# Top.net
KiCad netlist of a schematic drawn in Altium Designer
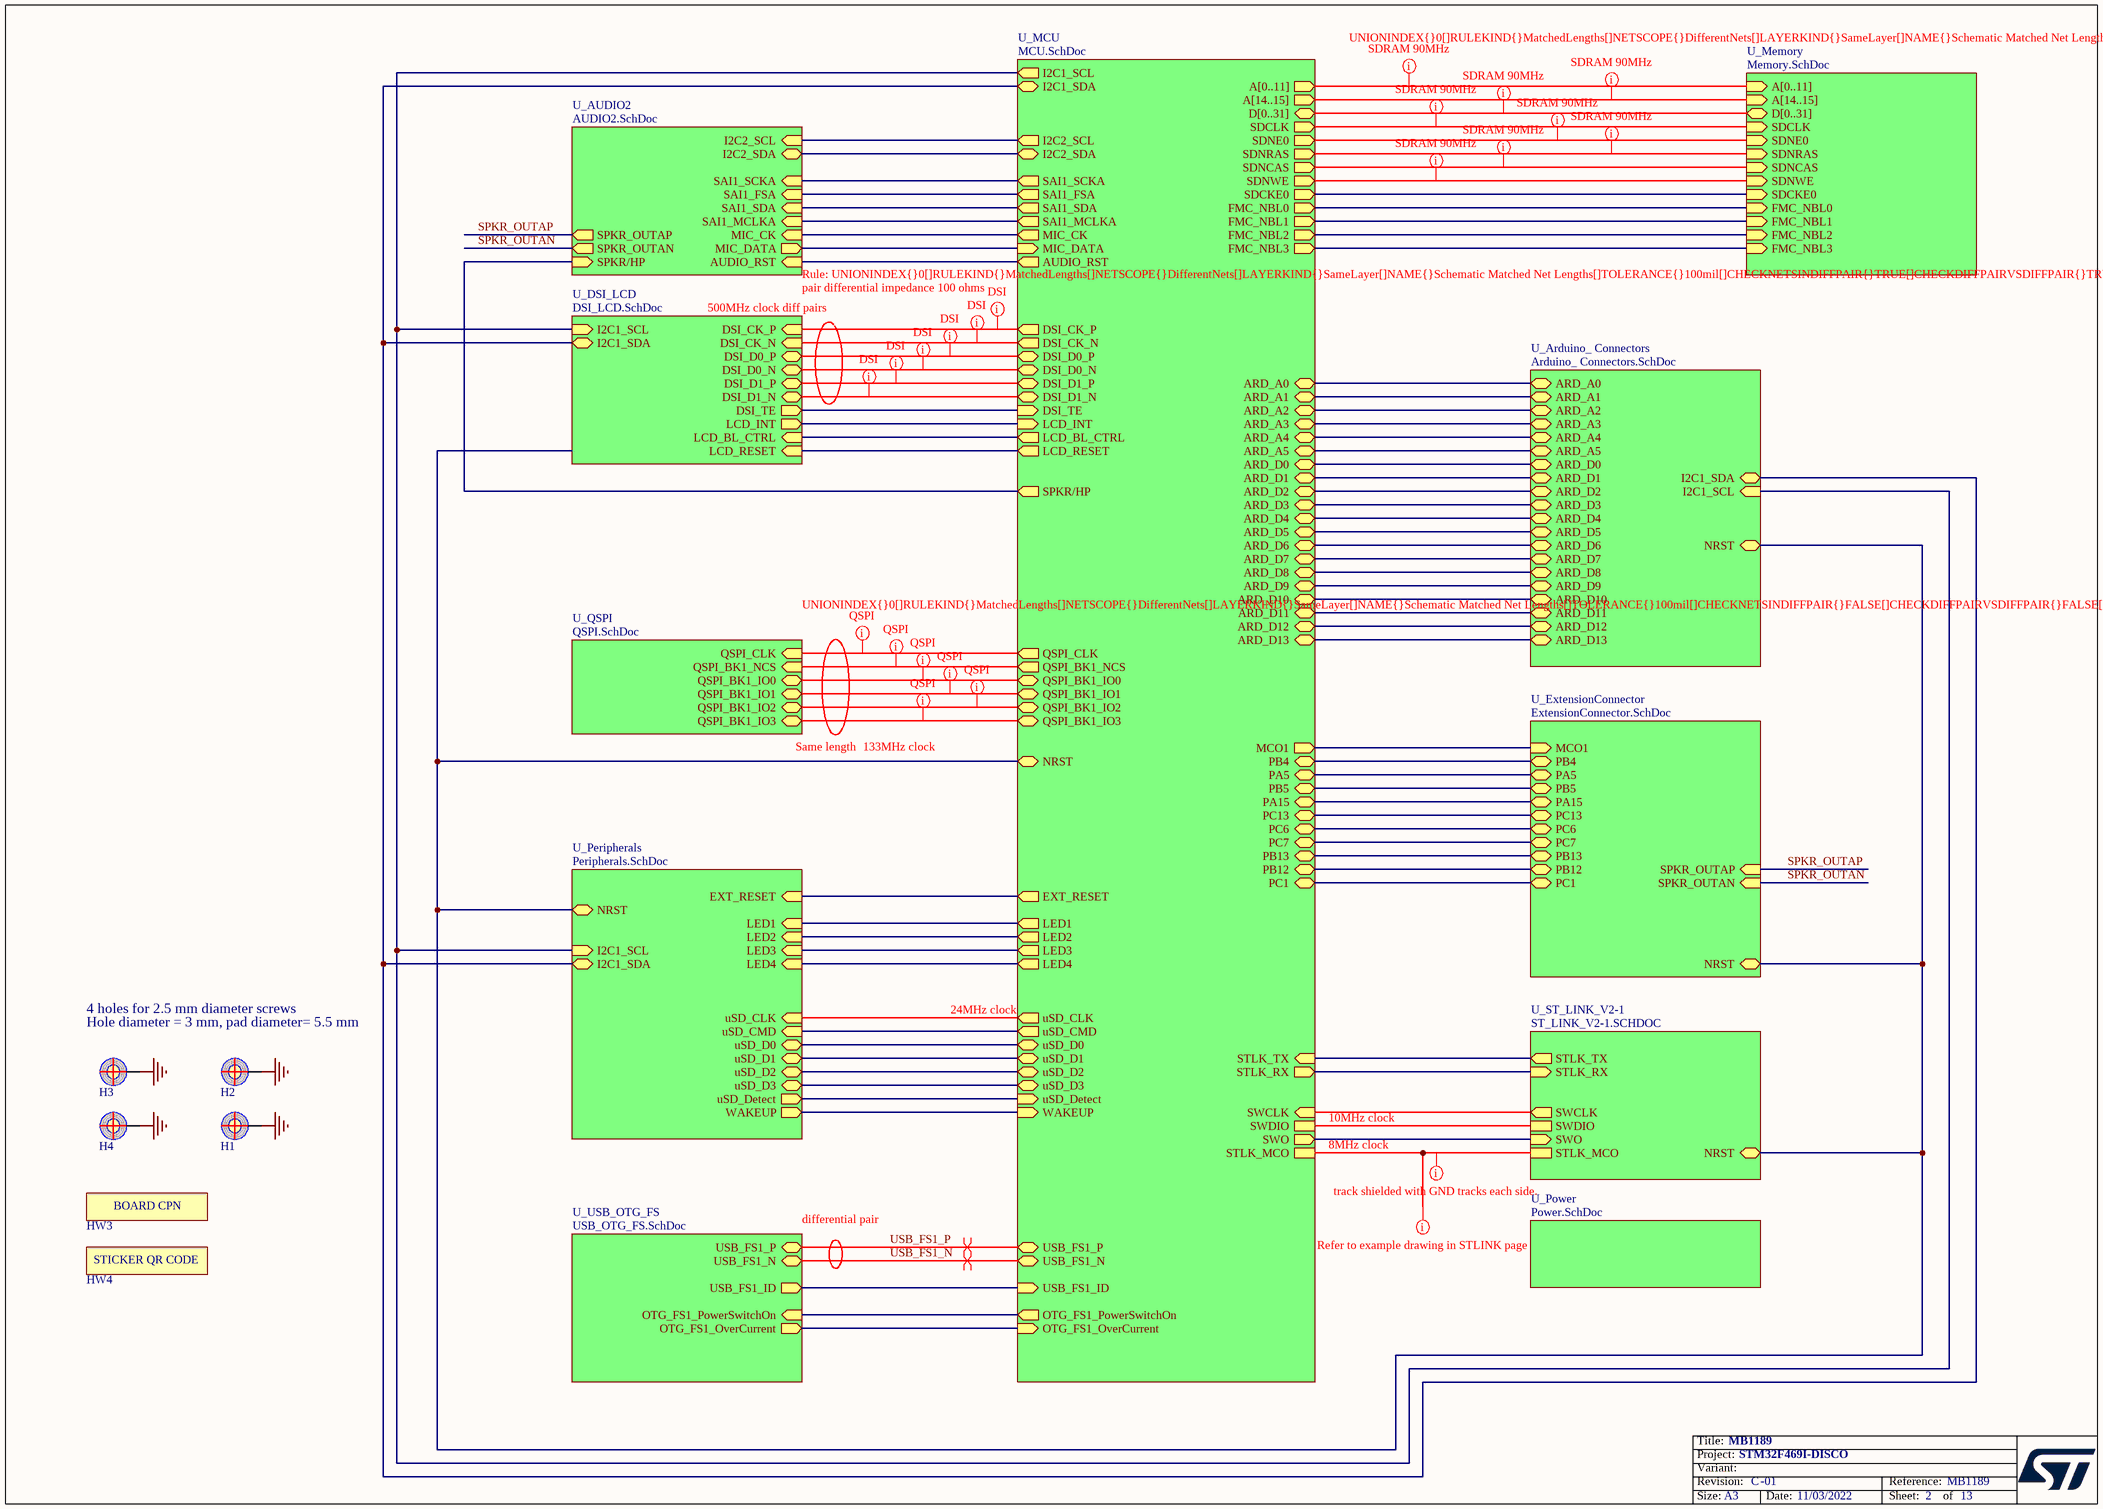
[diagram p0: Top.SchDoc]

(export (version "E")
  (design (tool "Eeschema 10.0.6"))
  (components
    (comp (ref "H1")
      (value "POSITION HOLE")
      (footprint "HOLE_C5R5D3")
      (libsource (lib "mb1045") (part "POSITION HOLE"))
    )
    (comp (ref "H2")
      (value "POSITION HOLE")
      (footprint "HOLE_C5R5D3")
      (libsource (lib "mb1045") (part "POSITION HOLE"))
    )
    (comp (ref "H3")
      (value "POSITION HOLE")
      (footprint "HOLE_C5R5D3")
      (libsource (lib "mb1045") (part "POSITION HOLE"))
    )
    (comp (ref "H4")
      (value "POSITION HOLE")
      (footprint "HOLE_C5R5D3")
      (libsource (lib "mb1045") (part "POSITION HOLE"))
    )
    (comp (ref "HW3")
      (value "STICKER_BOARD_CPN")
      (footprint "STICKER_BOARD-CPN_13X3")
      (libsource (lib "MB1189") (part "STICKER_BOARD_CPN"))
    )
    (comp (ref "HW4")
      (value "STICKER_QR_CODE")
      (footprint "STICKER_QR_CODE_8X8")
      (libsource (lib "MB1189") (part "STICKER_QR_CODE"))
    )
  )
  (nets
    (net (code "100") (name "GND") (class "Default")
      (node (ref "H1") (pin "1") (pinfunction "1_1") (pintype "passive"))
      (node (ref "H2") (pin "1") (pinfunction "1_1") (pintype "passive"))
      (node (ref "H3") (pin "1") (pinfunction "1_1") (pintype "passive"))
      (node (ref "H4") (pin "1") (pinfunction "1_1") (pintype "passive"))
    )
  )
)
